# Power.net
KiCad netlist of a schematic drawn in Altium Designer
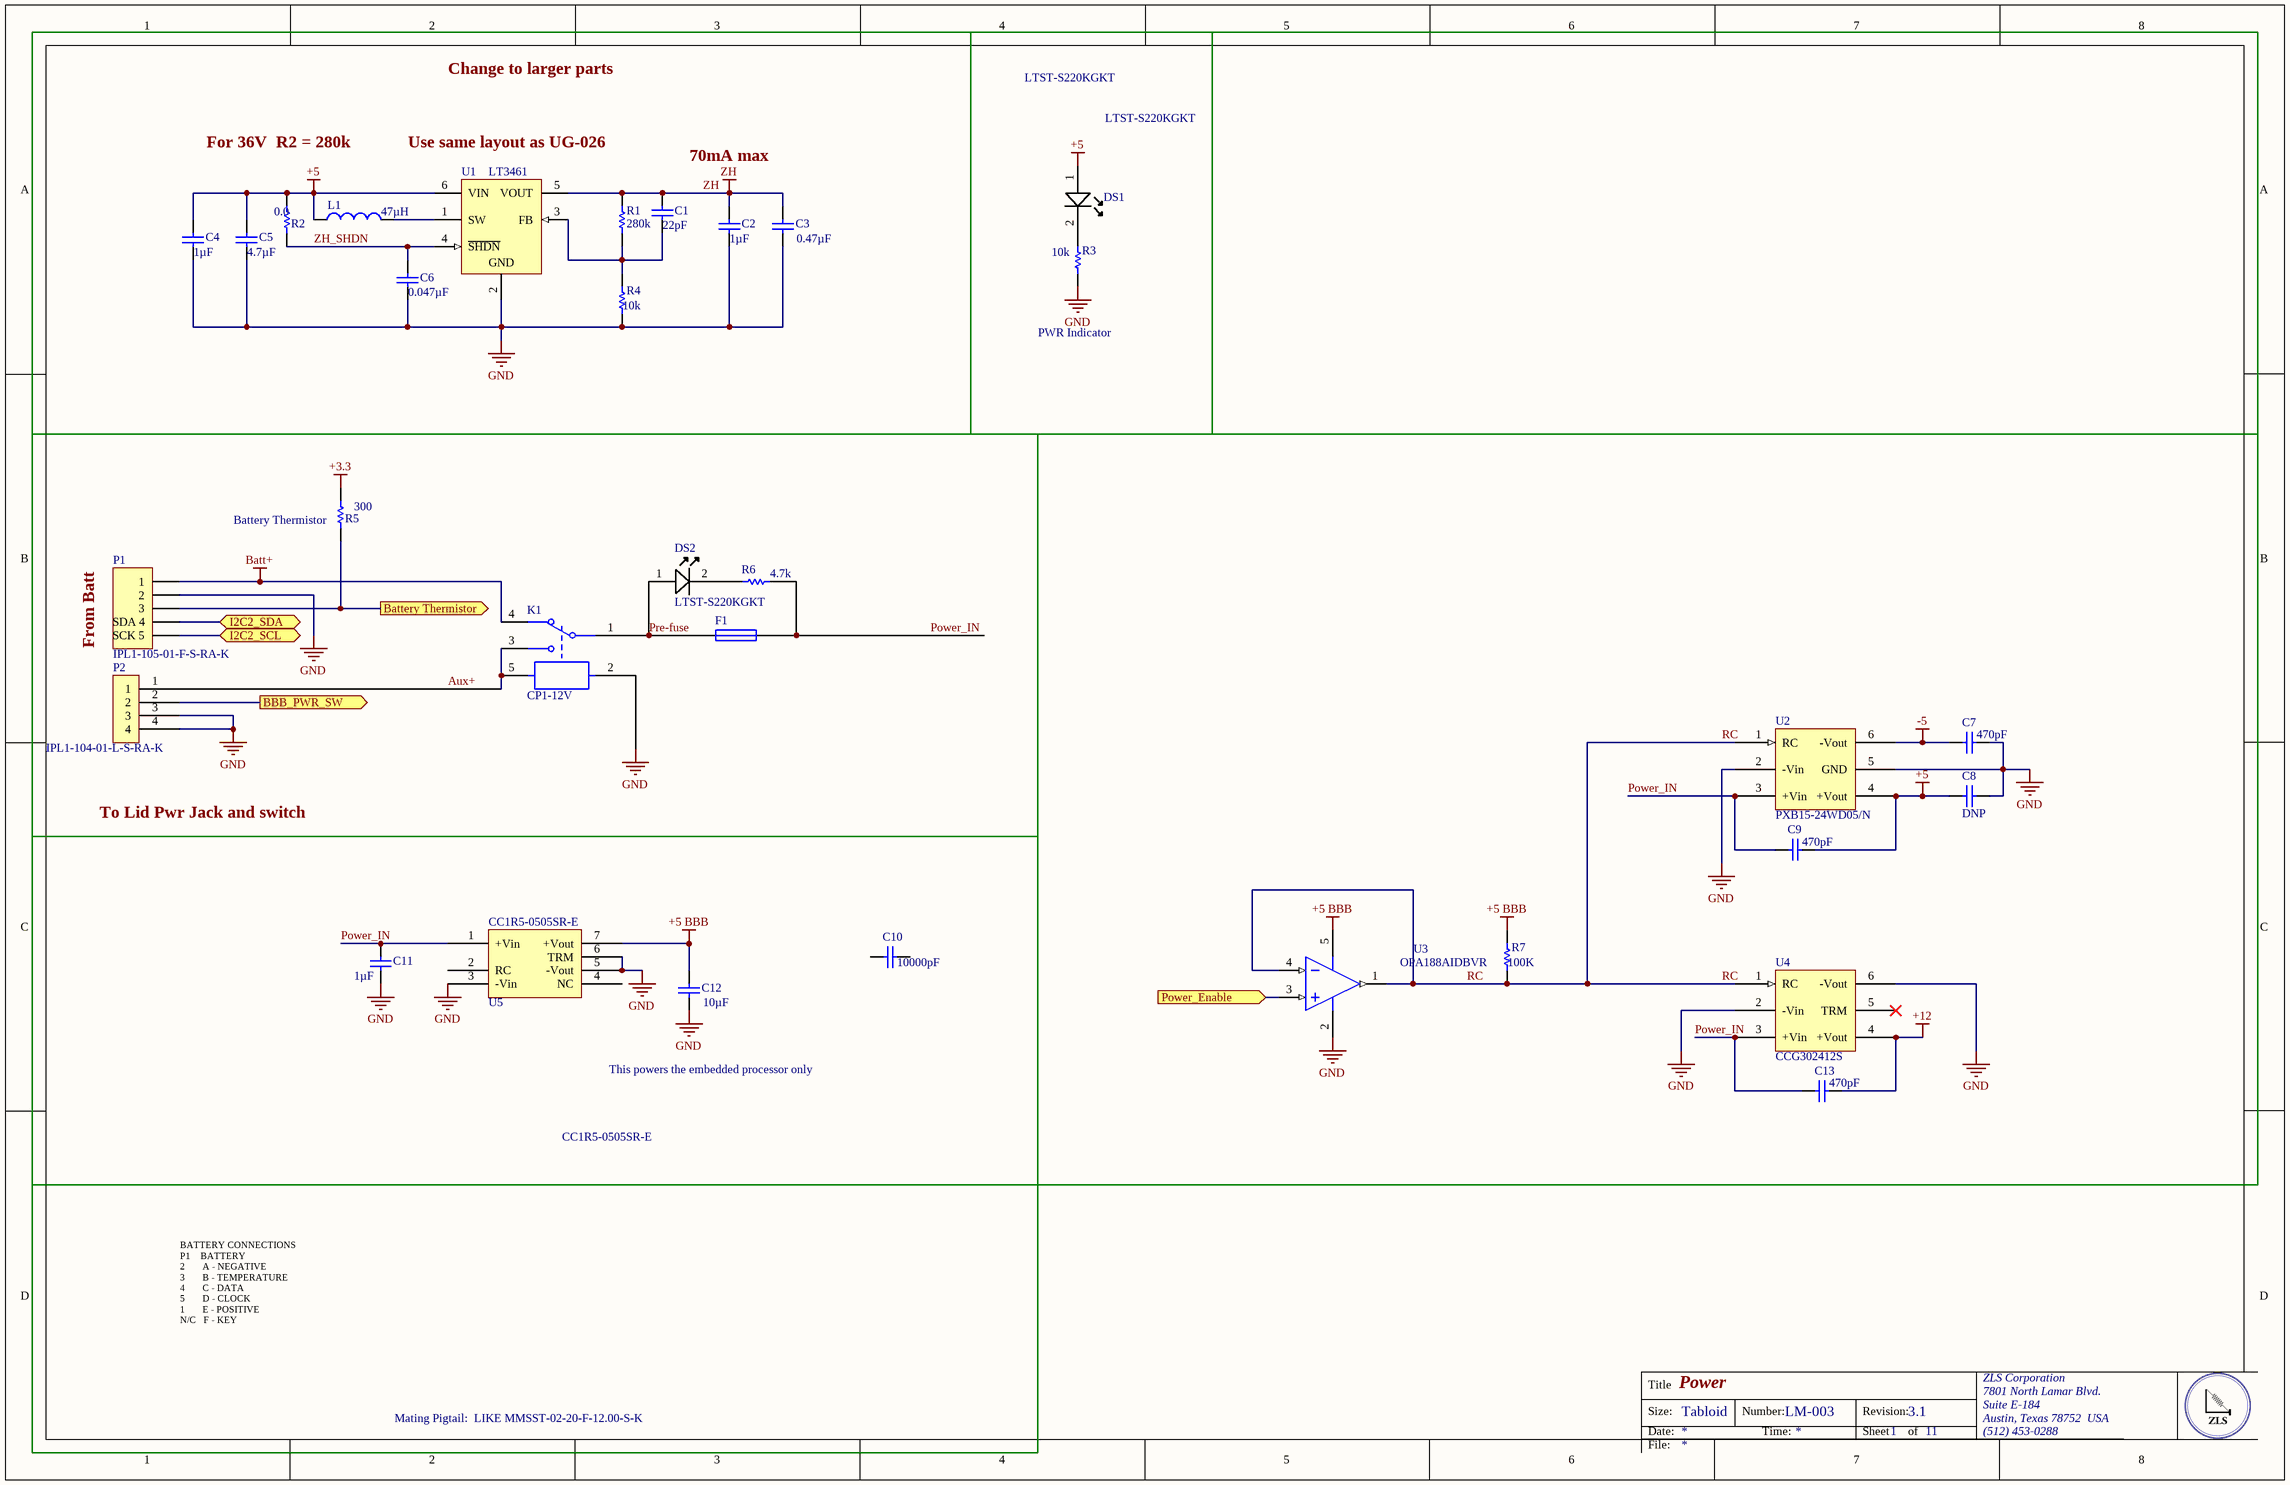
[diagram p0: Power.SchDoc]

(export (version "E")
  (design (tool "Eeschema 10.0.6"))
  (components
    (comp (ref "C1")
      (value "CAP CER 22PF 50V X7R 0603")
      (footprint "CAPC0603(1608)100_N")
      (fields
        (field (name "MANUFACTURER") "AVX Corporation")
        (field (name "MANUFACTURER PART NUMBER") "06035C220JAT2A")
        (field (name "CAPACITANCE") "22pF")
        (field (name "TOLERANCE") "±5%")
      )
      (libsource (lib "Altium Content Vault") (part "CMP-1035-00578-1"))
    )
    (comp (ref "C2")
      (value "CAP CER 1UF 50V X7R 1210")
      (footprint "CAPC1210(3225)100_N")
      (fields
        (field (name "MANUFACTURER") "Taiyo Yuden")
        (field (name "MANUFACTURER PART NUMBER") "UMK325B7105KH-T")
        (field (name "CAPACITANCE") "1µF")
        (field (name "TOLERANCE") "±10%")
      )
      (libsource (lib "Altium Content Vault") (part "CMP-1038-01123-1"))
    )
    (comp (ref "C3")
      (value "CAP CER 0.47UF 50V X7R 1206")
      (footprint "CAPC1206(3216)190_N")
      (fields
        (field (name "MANUFACTURER") "Taiyo Yuden")
        (field (name "MANUFACTURER PART NUMBER") "UMK316B7474KL-T")
        (field (name "CAPACITANCE") "0.47µF")
        (field (name "TOLERANCE") "±10%")
      )
      (libsource (lib "Altium Content Vault") (part "CMP-1037-04570-1"))
    )
    (comp (ref "C4")
      (value "CAP CER 1UF 16V X7R 0805")
      (footprint "CAPC0805(2012)145_N")
      (fields
        (field (name "MANUFACTURER") "Taiyo Yuden")
        (field (name "MANUFACTURER PART NUMBER") "EMK212B7105KG-T")
        (field (name "CAPACITANCE") "1µF")
        (field (name "TOLERANCE") "±10%")
      )
      (libsource (lib "Altium Content Vault") (part "CMP-1036-04795-1"))
    )
    (comp (ref "C5")
      (value "CAP CER 4.7UF 16V X7R 1206")
      (footprint "CAPC1206(3216)130_N")
      (fields
        (field (name "MANUFACTURER") "Taiyo Yuden")
        (field (name "MANUFACTURER PART NUMBER") "EMK316B7475KL-T")
        (field (name "CAPACITANCE") "4.7µF")
        (field (name "TOLERANCE") "±10%")
      )
      (libsource (lib "Altium Content Vault") (part "CMP-1037-04913-1"))
    )
    (comp (ref "C6")
      (value "CAP CER 0.047UF 16V X7R 0603")
      (footprint "CAPC0805(2012)145_N")
      (fields
        (field (name "MANUFACTURER") "Murata Electronics North America")
        (field (name "MANUFACTURER PART NUMBER") "GRM188R71C473KA01D")
        (field (name "CAPACITANCE") "0.047µF")
        (field (name "TOLERANCE") "±10%")
      )
      (libsource (lib "Altium Content Vault") (part "CMP-1036-04795-1"))
    )
    (comp (ref "C7")
      (value "CAP CER 470PF 3KV X7R 1812")
      (footprint "CAPC1812(4532)230_M")
      (fields
        (field (name "MANUFACTURER") "Kemet")
        (field (name "MANUFACTURER PART NUMBER") "C1812C471KHRACTU")
        (field (name "CAPACITANCE") "470pF")
        (field (name "TOLERANCE") "10%")
      )
      (libsource (lib "Altium Content Vault") (part "CMP-1040-00561-1"))
    )
    (comp (ref "C8")
      (value "DNP")
      (footprint "CAPC1812(4532)230_M")
      (description "CAP CER 470PF 3KV X7R 1812")
      (fields
        (field (name "MANUFACTURER") "Kemet")
        (field (name "MANUFACTURER PART NUMBER") "C1812C471KHRACTU")
      )
      (libsource (lib "Altium Content Vault") (part "CMP-1040-00561-1"))
    )
    (comp (ref "C9")
      (value "CAP CER 470PF 3KV X7R 1812")
      (footprint "CAPC1812(4532)230_M")
      (fields
        (field (name "MANUFACTURER") "Kemet")
        (field (name "MANUFACTURER PART NUMBER") "C1812C471KHRACTU")
        (field (name "CAPACITANCE") "470pF")
        (field (name "TOLERANCE") "10%")
      )
      (libsource (lib "Altium Content Vault") (part "CMP-1040-00561-1"))
    )
    (comp (ref "C10")
      (value "CAP CER 10000PF 25V X7R 0805")
      (footprint "CAPC0805(2012)145_N")
      (fields
        (field (name "MANUFACTURER") "Murata Electronics North America")
        (field (name "MANUFACTURER PART NUMBER") "GRM216R71E103KA01D")
        (field (name "CAPACITANCE") "10000pF")
        (field (name "TOLERANCE") "±10%")
      )
      (libsource (lib "Altium Content Vault") (part "CMP-1036-04795-1"))
    )
    (comp (ref "C11")
      (value "CAP CER 1UF 50V X7R 1210")
      (footprint "CAPC1210(3225)100_L")
      (fields
        (field (name "MANUFACTURER") "Murata Electronics North America")
        (field (name "MANUFACTURER PART NUMBER") "GRM32RR71H105KA01L")
        (field (name "CAPACITANCE") "1µF")
        (field (name "TOLERANCE") "±10%")
      )
      (libsource (lib "Altium Content Vault") (part "CMP-1038-00632-1"))
    )
    (comp (ref "C12")
      (value "CAP CER 10UF 10V X7R 0805")
      (footprint "CAPC0805(2012)145_N")
      (fields
        (field (name "MANUFACTURER") "Murata Electronics North America")
        (field (name "MANUFACTURER PART NUMBER") "GCM21BR71A106KE22L")
        (field (name "CAPACITANCE") "10µF")
        (field (name "TOLERANCE") "±10%")
      )
      (libsource (lib "Altium Content Vault") (part "CMP-1036-04795-1"))
    )
    (comp (ref "C13")
      (value "CAP CER 470PF 3KV X7R 1812")
      (footprint "CAPC1812(4532)230_M")
      (fields
        (field (name "MANUFACTURER") "Kemet")
        (field (name "MANUFACTURER PART NUMBER") "C1812C471KHRACTU")
        (field (name "CAPACITANCE") "470pF")
        (field (name "TOLERANCE") "10%")
      )
      (libsource (lib "Altium Content Vault") (part "CMP-1040-00561-1"))
    )
    (comp (ref "DS1")
      (value "Lite-On LTST-S220KGKT Green LED, 571 nm 2012 (0805) Side View, Rectangle Lens SMD package")
      (footprint "0805C_L")
      (fields
        (field (name "MANUFACTURER") "Vishay / Lite-On")
        (field (name "MANUFACTURER PART NUMBER") "LTST-S220KGKT")
      )
      (libsource (lib "*") (part "LED A/K"))
    )
    (comp (ref "DS2")
      (value "Lite-On LTST-S220KGKT Green LED, 571 nm 2012 (0805) Side View, Rectangle Lens SMD package")
      (footprint "0805C_L")
      (fields
        (field (name "MANUFACTURER") "Vishay / Lite-On")
        (field (name "MANUFACTURER PART NUMBER") "LTST-S220KGKT")
      )
      (libsource (lib "*") (part "LED A/K"))
    )
    (comp (ref "F1")
      (value "Fuse 1")
      (footprint "PIN-W2/E2.8")
      (description "Fuse")
      (fields (field (name "PUBLISHER") "Altium Limited"))
      (libsource (lib "Miscellaneous Devices") (part "Fuse 1"))
    )
    (comp (ref "K1")
      (value "CP1-12V")
      (footprint "PNSC-CP1-12V_V")
      (description "1 Form C SPDT Relay, 12 VDC, 40 A, -40 to 85 degC, 5-Pin THD, RoHS, Tube")
      (fields (field (name "MANUFACTURER") "Panasonic"))
      (libsource (lib "Altium Content Vault") (part "CMP-2000-06116-1"))
    )
    (comp (ref "L1")
      (value "FIXED IND 47UH 170MA 1.3 OHM SMD")
      (footprint "0402-A")
      (fields (field (name "INDUCTANCE") "47µH") (field (name "TOLERANCE") "±10%"))
      (libsource (lib "Miscellaneous Devices") (part "Inductor"))
    )
    (comp (ref "P1")
      (value "IPL1-105-01-F-S-RA-K")
      (footprint "IPL1-105-1")
      (description "Header, 5-Pin, Right Angle")
      (libsource (lib "Miscellaneous Connectors") (part "Header 5H"))
    )
    (comp (ref "P2")
      (value "IPL1-104-01-L-S-RA-K")
      (footprint "IPL1-104-01")
      (description ".100 TERMINAL ASSY")
      (libsource (lib "ZLS_LIB") (part "53047-0410"))
    )
    (comp (ref "R1")
      (value "RES SMD 280K OHM 1% 1/8W 0805")
      (footprint "RESC0805(2012)_M")
      (fields
        (field (name "MANUFACTURER") "Vishay Dale")
        (field (name "MANUFACTURER PART NUMBER") "CRCW0805280KFKEA")
        (field (name "RESISTANCE (OHMS)") "280k")
        (field (name "TOLERANCE") "±1%")
      )
      (libsource (lib "Altium Content Vault") (part "CMP-1013-00017-1"))
    )
    (comp (ref "R2")
      (value "RES SMD 0.0 OHM JUMPER 1/8W 0805")
      (footprint "RESC0805(2012)_M")
      (fields
        (field (name "MANUFACTURER") "Vishay Dale")
        (field (name "MANUFACTURER PART NUMBER") "CRCW08050000Z0EA")
        (field (name "RESISTANCE (OHMS)") "0.0")
        (field (name "TOLERANCE") "Jumper")
      )
      (libsource (lib "Altium Content Vault") (part "CMP-1013-00017-1"))
    )
    (comp (ref "R3")
      (value "RES SMD 10K OHM 1% 1/8W 0805")
      (footprint "RESC0805(2012)_M")
      (fields
        (field (name "MANUFACTURER") "Vishay Dale")
        (field (name "MANUFACTURER PART NUMBER") "CRCW080510K0FKTA")
        (field (name "RESISTANCE (OHMS)") "10k")
        (field (name "TOLERANCE") "±1%")
      )
      (libsource (lib "Altium Content Vault") (part "CMP-1013-00017-1"))
    )
    (comp (ref "R4")
      (value "RES SMD 10K OHM 1% 1/8W 0805")
      (footprint "RESC0805(2012)_M")
      (fields
        (field (name "MANUFACTURER") "Yageo")
        (field (name "MANUFACTURER PART NUMBER") "RC0805FR-0710KL")
        (field (name "RESISTANCE (OHMS)") "10k")
        (field (name "TOLERANCE") "±1%")
      )
      (libsource (lib "Altium Content Vault") (part "CMP-1013-00017-1"))
    )
    (comp (ref "R5")
      (value "300K 5% 0805(2012)")
      (footprint "RESC0805(2012)_M")
      (description "300K 0.125W 5% 0805 (2012 Metric)  SMD")
      (fields
        (field (name "MANUFACTURER") "Vishay Dale")
        (field (name "MANUFACTURER PART NUMBER") "CRCW0805300RFKEA")
        (field (name "RESISTANCE (OHMS)") "300")
      )
      (libsource (lib "Altium Content Vault") (part "CMP-1013-00133-1"))
    )
    (comp (ref "R6")
      (value "RES SMD 4.7K OHM 1% 1/8W 0805")
      (footprint "RESC0805(2012)_M")
      (fields
        (field (name "MANUFACTURER") "Vishay Dale")
        (field (name "MANUFACTURER PART NUMBER") "CRCW08054K70FKEA")
        (field (name "RESISTANCE (OHMS)") "4.7k")
        (field (name "TOLERANCE") "±1%")
      )
      (libsource (lib "Altium Content Vault") (part "CMP-1013-00017-1"))
    )
    (comp (ref "R7")
      (value "RES SMD 100K OHM 1% 1/8W 0805")
      (footprint "RESC0805(2012)_M")
      (fields
        (field (name "MANUFACTURER") "Vishay")
        (field (name "MANUFACTURER PART NUMBER") "CRCW0805100KFKEA")
        (field (name "TOLERANCE") "1%")
        (field (name "RESISTANCE") "100K")
      )
      (libsource (lib "Altium Content Vault") (part "CMP-1013-00017-1"))
    )
    (comp (ref "U1")
      (value "LT3461")
      (footprint "LT-S6-6-TSOT-23_N")
      (description "IC REG BOOST ADJ 0.3A TSOT23-6")
      (libsource (lib "Altium Content Vault") (part "CMP-0491-01698-1"))
    )
    (comp (ref "U2")
      (value "PXB15-24WD05/N")
      (footprint "PXB15-24WD05/N")
      (description "IC CONV DC-DC 15W DUAL 5V PCB")
      (libsource (lib "") (part "CCG302412S_1"))
    )
    (comp (ref "U3")
      (value "OPA188AIDBVR")
      (footprint "DBV0005A_M")
      (fields (field (name "MANUFACTURER") "Texas Instruments"))
      (libsource (lib "Altium Content Vault") (part "CMP-0809-00005-2"))
    )
    (comp (ref "U4")
      (value "CCG302412S")
      (footprint "CCG30")
      (description "DC/DC CONVERTER 12V 2.5A PCB")
      (libsource (lib "ZLS_LIB") (part "CCG302412S"))
    )
    (comp (ref "U5")
      (value "CC1R5-0505SR-E")
      (footprint "CC1R5-0505SR-E")
      (description "CONV DC/DC 1.5W SNGL 5V 5V SMD")
      (fields
        (field (name "MANUFACTURER") "TDK-Lambda Americas Inc.")
        (field (name "MANUFACTURER PART NUMBER") "CC1R5-0505SR-E")
      )
      (libsource (lib "ZLS_Schematic_lib") (part "CC1R5-0505SR-E"))
    )
  )
  (nets
    (net (code "1") (name "+3.3") (class "Default")
      (node (ref "R5") (pin "2") (pinfunction "2_2") (pintype "passive"))
    )
    (net (code "2") (name "+5") (class "Default")
      (node (ref "C4") (pin "2") (pinfunction "2_2") (pintype "passive"))
      (node (ref "C5") (pin "2") (pinfunction "2_2") (pintype "passive"))
      (node (ref "C8") (pin "1") (pinfunction "1_1") (pintype "passive"))
      (node (ref "C9") (pin "2") (pinfunction "2_2") (pintype "passive"))
      (node (ref "DS1") (pin "1") (pinfunction "A_1") (pintype "passive"))
      (node (ref "L1") (pin "1") (pinfunction "1_1") (pintype "passive"))
      (node (ref "R2") (pin "1") (pinfunction "1_1") (pintype "passive"))
      (node (ref "U1") (pin "6") (pinfunction "VIN_6") (pintype "power_in"))
      (node (ref "U2") (pin "4") (pinfunction "+Vout_4") (pintype "power_in"))
    )
    (net (code "3") (name "+5 BBB") (class "Default")
      (node (ref "C12") (pin "2") (pinfunction "2_2") (pintype "passive"))
      (node (ref "R7") (pin "1") (pinfunction "1_1") (pintype "passive"))
      (node (ref "U3") (pin "5") (pinfunction "V+_5") (pintype "power_in"))
      (node (ref "U5") (pin "7") (pinfunction "+Vout_7") (pintype "passive"))
    )
    (net (code "4") (name "+12") (class "Default")
      (node (ref "C13") (pin "2") (pinfunction "2_2") (pintype "passive"))
      (node (ref "U4") (pin "4") (pinfunction "+Vout_4") (pintype "power_in"))
    )
    (net (code "5") (name "-5") (class "Default")
      (node (ref "C7") (pin "1") (pinfunction "1_1") (pintype "passive"))
      (node (ref "U2") (pin "6") (pinfunction "-Vout_6") (pintype "power_in"))
    )
    (net (code "6") (name "/Aux+") (class "Default")
      (node (ref "K1") (pin "3") (pinfunction "3_3") (pintype "passive"))
      (node (ref "K1") (pin "5") (pinfunction "5_5") (pintype "passive"))
      (node (ref "P2") (pin "1") (pinfunction "1_1") (pintype "passive"))
    )
    (net (code "7") (name "/BBB_PWR_SW") (class "Default")
      (node (ref "P2") (pin "2") (pinfunction "2_2") (pintype "passive"))
    )
    (net (code "8") (name "/Battery Thermistor") (class "Default")
      (node (ref "P1") (pin "3") (pinfunction "3_3") (pintype "passive"))
      (node (ref "R5") (pin "1") (pinfunction "1_1") (pintype "passive"))
    )
    (net (code "9") (name "/I2C2_SCL") (class "Default")
      (node (ref "P1") (pin "5") (pinfunction "SCK_5_5") (pintype "passive"))
    )
    (net (code "10") (name "/I2C2_SDA") (class "Default")
      (node (ref "P1") (pin "4") (pinfunction "SDA_4_4") (pintype "passive"))
    )
    (net (code "11") (name "/Power_Enable") (class "Default")
      (node (ref "U3") (pin "3") (pinfunction "IN+_3") (pintype "input"))
    )
    (net (code "12") (name "/Power_IN") (class "Default")
      (node (ref "C11") (pin "2") (pinfunction "2_2") (pintype "passive"))
      (node (ref "C13") (pin "1") (pinfunction "1_1") (pintype "passive"))
      (node (ref "C9") (pin "1") (pinfunction "1_1") (pintype "passive"))
      (node (ref "F1") (pin "2") (pinfunction "2_2") (pintype "passive"))
      (node (ref "R6") (pin "1") (pinfunction "1_1") (pintype "passive"))
      (node (ref "U2") (pin "3") (pinfunction "+Vin_3") (pintype "power_in"))
      (node (ref "U4") (pin "3") (pinfunction "+Vin_3") (pintype "passive"))
      (node (ref "U5") (pin "1") (pinfunction "+Vin_1") (pintype "passive"))
    )
    (net (code "13") (name "/Pre-fuse") (class "Default")
      (node (ref "DS2") (pin "1") (pinfunction "A_1") (pintype "passive"))
      (node (ref "F1") (pin "1") (pinfunction "1_1") (pintype "passive"))
      (node (ref "K1") (pin "1") (pinfunction "1_1") (pintype "passive"))
    )
    (net (code "14") (name "/RC") (class "Default")
      (node (ref "R7") (pin "2") (pinfunction "2_2") (pintype "passive"))
      (node (ref "U2") (pin "1") (pinfunction "RC_1") (pintype "input"))
      (node (ref "U3") (pin "1") (pinfunction "OUT_1") (pintype "output"))
      (node (ref "U3") (pin "4") (pinfunction "IN-_4") (pintype "input"))
      (node (ref "U4") (pin "1") (pinfunction "RC_1") (pintype "input"))
    )
    (net (code "15") (name "/ZH_SHDN") (class "Default")
      (node (ref "C6") (pin "2") (pinfunction "2_2") (pintype "passive"))
      (node (ref "R2") (pin "2") (pinfunction "2_2") (pintype "passive"))
      (node (ref "U1") (pin "4") (pinfunction "~{SHDN}_4") (pintype "input"))
    )
    (net (code "16") (name "Batt+") (class "Default")
      (node (ref "K1") (pin "4") (pinfunction "4_4") (pintype "passive"))
      (node (ref "P1") (pin "1") (pinfunction "1_1") (pintype "passive"))
    )
    (net (code "17") (name "GND") (class "Default")
      (node (ref "C11") (pin "1") (pinfunction "1_1") (pintype "passive"))
      (node (ref "C12") (pin "1") (pinfunction "1_1") (pintype "passive"))
      (node (ref "C2") (pin "1") (pinfunction "1_1") (pintype "passive"))
      (node (ref "C3") (pin "1") (pinfunction "1_1") (pintype "passive"))
      (node (ref "C4") (pin "1") (pinfunction "1_1") (pintype "passive"))
      (node (ref "C5") (pin "1") (pinfunction "1_1") (pintype "passive"))
      (node (ref "C6") (pin "1") (pinfunction "1_1") (pintype "passive"))
      (node (ref "C7") (pin "2") (pinfunction "2_2") (pintype "passive"))
      (node (ref "C8") (pin "2") (pinfunction "2_2") (pintype "passive"))
      (node (ref "K1") (pin "2") (pinfunction "2_2") (pintype "passive"))
      (node (ref "P1") (pin "2") (pinfunction "2_2") (pintype "passive"))
      (node (ref "P2") (pin "3") (pinfunction "3_3") (pintype "passive"))
      (node (ref "P2") (pin "4") (pinfunction "4_4") (pintype "passive"))
      (node (ref "R3") (pin "1") (pinfunction "1_1") (pintype "passive"))
      (node (ref "R4") (pin "2") (pinfunction "2_2") (pintype "passive"))
      (node (ref "U1") (pin "2") (pinfunction "GND_2") (pintype "power_in"))
      (node (ref "U2") (pin "2") (pinfunction "-Vin_2") (pintype "power_in"))
      (node (ref "U2") (pin "5") (pinfunction "GND_5") (pintype "power_in"))
      (node (ref "U3") (pin "2") (pinfunction "V-_2") (pintype "power_in"))
      (node (ref "U4") (pin "2") (pinfunction "-Vin_2") (pintype "power_in"))
      (node (ref "U4") (pin "6") (pinfunction "-Vout_6") (pintype "power_in"))
      (node (ref "U5") (pin "3") (pinfunction "-Vin_3") (pintype "passive"))
      (node (ref "U5") (pin "5") (pinfunction "-Vout_5") (pintype "passive"))
      (node (ref "U5") (pin "6") (pinfunction "TRM_6") (pintype "passive"))
    )
    (net (code "18") (name "Net-(DS1-K)") (class "Default")
      (node (ref "DS1") (pin "2") (pinfunction "K_2") (pintype "passive"))
      (node (ref "R3") (pin "2") (pinfunction "2_2") (pintype "passive"))
    )
    (net (code "19") (name "Net-(DS2-K)") (class "Default")
      (node (ref "DS2") (pin "2") (pinfunction "K_2") (pintype "passive"))
      (node (ref "R6") (pin "2") (pinfunction "2_2") (pintype "passive"))
    )
    (net (code "20") (name "Net-(U1-FB)") (class "Default")
      (node (ref "C1") (pin "1") (pinfunction "1_1") (pintype "passive"))
      (node (ref "R1") (pin "2") (pinfunction "2_2") (pintype "passive"))
      (node (ref "R4") (pin "1") (pinfunction "1_1") (pintype "passive"))
      (node (ref "U1") (pin "3") (pinfunction "FB_3") (pintype "input"))
    )
    (net (code "21") (name "Net-(U1-SW)") (class "Default")
      (node (ref "L1") (pin "2") (pinfunction "2_2") (pintype "passive"))
      (node (ref "U1") (pin "1") (pinfunction "SW_1") (pintype "passive"))
    )
    (net (code "22") (name "ZH") (class "Default")
      (node (ref "C1") (pin "2") (pinfunction "2_2") (pintype "passive"))
      (node (ref "C2") (pin "2") (pinfunction "2_2") (pintype "passive"))
      (node (ref "C3") (pin "2") (pinfunction "2_2") (pintype "passive"))
      (node (ref "R1") (pin "1") (pinfunction "1_1") (pintype "passive"))
      (node (ref "U1") (pin "5") (pinfunction "VOUT_5") (pintype "power_in"))
    )
    (net (code "23") (name "unconnected-(C10-Pad1)") (class "Default")
      (node (ref "C10") (pin "1") (pinfunction "1_1") (pintype "passive"))
    )
    (net (code "24") (name "unconnected-(C10-Pad2)") (class "Default")
      (node (ref "C10") (pin "2") (pinfunction "2_2") (pintype "passive"))
    )
    (net (code "25") (name "unconnected-(U4-TRM-Pad5)") (class "Default")
      (node (ref "U4") (pin "5") (pinfunction "TRM_5") (pintype "passive+no_connect"))
    )
    (net (code "26") (name "unconnected-(U5-NC-Pad4)") (class "Default")
      (node (ref "U5") (pin "4") (pinfunction "NC_4") (pintype "passive"))
    )
    (net (code "27") (name "unconnected-(U5-RC-Pad2)") (class "Default")
      (node (ref "U5") (pin "2") (pinfunction "RC_2") (pintype "passive"))
    )
  )
)
